# Schematic_v10.net
KiCad netlist of a schematic drawn in EAGLE
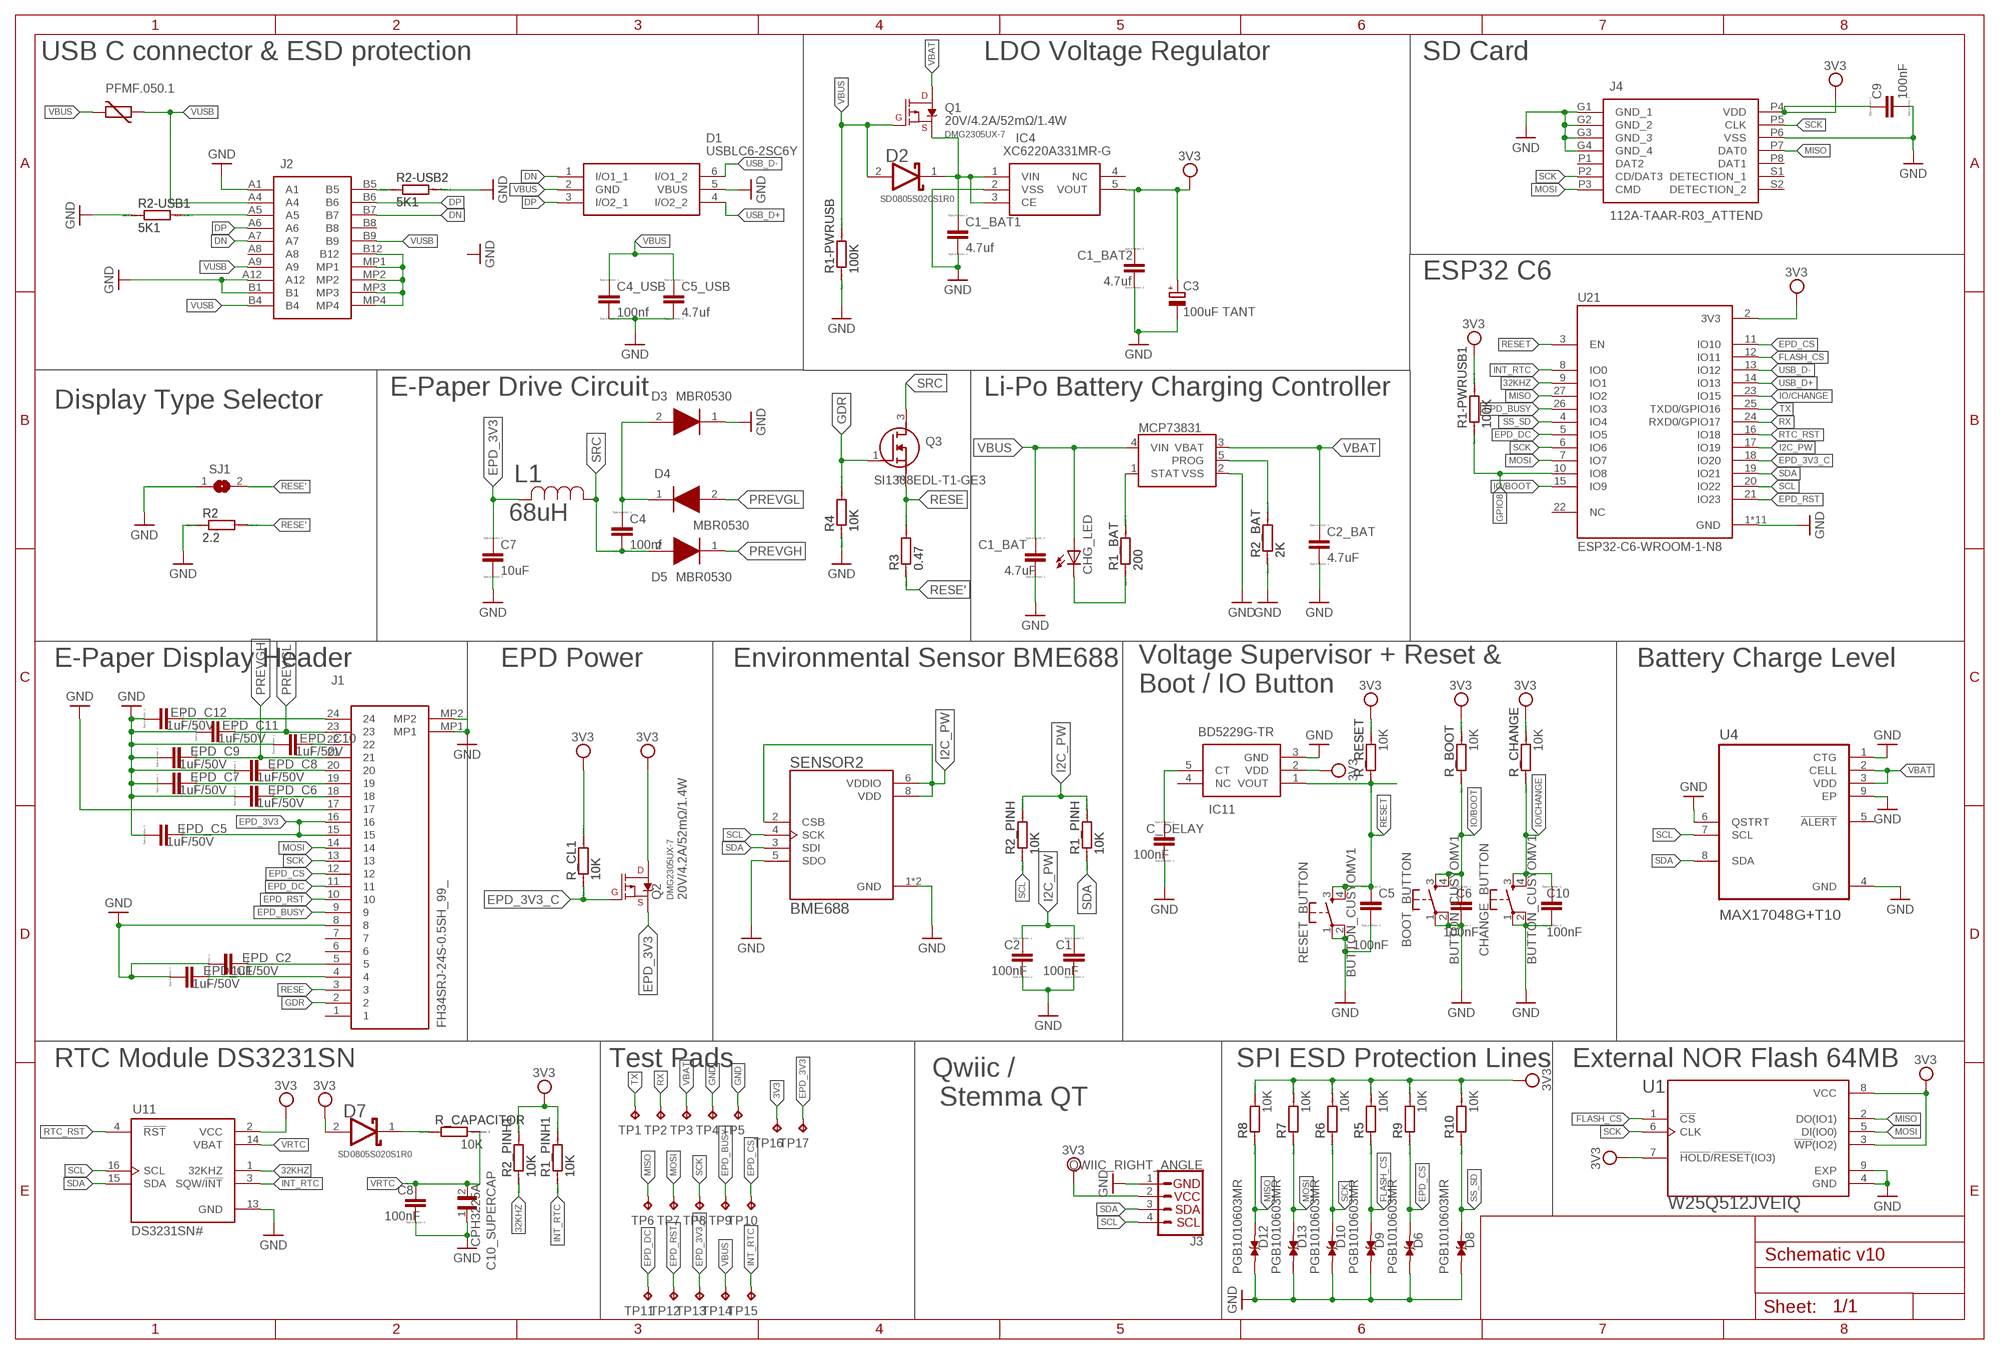
[diagram p0: schematic, sheet 1]

(export (version "E")
  (design (tool "Eeschema 10.0.6"))
  (components
    (comp (ref "BOOT_BUTTON")
      (value "BUTTON_CUSYOMV1")
      (footprint "eagle-import:MYBUTTON")
      (libsource (lib "eagle-import") (part "BUTTON_CUSYOMV1"))
    )
    (comp (ref "C1")
      (value "100nF")
      (footprint "eagle-import:EAGLE-LTSPICE_C0402")
      (libsource (lib "eagle-import") (part "EAGLE-LTSPICE_CC0402"))
    )
    (comp (ref "C1_BAT")
      (value "4.7uF")
      (footprint "eagle-import:EAGLE-LTSPICE_C0402")
      (libsource (lib "eagle-import") (part "EAGLE-LTSPICE_CC0402"))
    )
    (comp (ref "C1_BAT1")
      (value "4.7uf")
      (footprint "eagle-import:EAGLE-LTSPICE_C0402")
      (libsource (lib "eagle-import") (part "EAGLE-LTSPICE_CC0402"))
    )
    (comp (ref "C1_BAT2")
      (value "4.7uf")
      (footprint "eagle-import:EAGLE-LTSPICE_C0402")
      (libsource (lib "eagle-import") (part "EAGLE-LTSPICE_CC0402"))
    )
    (comp (ref "C2")
      (value "100nF")
      (footprint "eagle-import:EAGLE-LTSPICE_C0402")
      (libsource (lib "eagle-import") (part "EAGLE-LTSPICE_CC0402"))
    )
    (comp (ref "C2_BAT")
      (value "4.7uF")
      (footprint "eagle-import:EAGLE-LTSPICE_C0402")
      (libsource (lib "eagle-import") (part "EAGLE-LTSPICE_CC0402"))
    )
    (comp (ref "C3")
      (value "100uF TANT")
      (footprint "eagle-import:RCL_CT3528")
      (libsource (lib "eagle-import") (part "RCL_CPOL-EUCT3528"))
    )
    (comp (ref "C4")
      (value "100nf")
      (footprint "eagle-import:EAGLE-LTSPICE_C0402")
      (libsource (lib "eagle-import") (part "EAGLE-LTSPICE_CC0402"))
    )
    (comp (ref "C4_USB")
      (value "100nf")
      (footprint "eagle-import:EAGLE-LTSPICE_C0402")
      (libsource (lib "eagle-import") (part "EAGLE-LTSPICE_CC0402"))
    )
    (comp (ref "C5")
      (value "100nF")
      (footprint "eagle-import:EAGLE-LTSPICE_C0402")
      (libsource (lib "eagle-import") (part "EAGLE-LTSPICE_CC0402"))
    )
    (comp (ref "C5_USB")
      (value "4.7uf")
      (footprint "eagle-import:EAGLE-LTSPICE_C0402")
      (libsource (lib "eagle-import") (part "EAGLE-LTSPICE_CC0402"))
    )
    (comp (ref "C6")
      (value "100nF")
      (footprint "eagle-import:EAGLE-LTSPICE_C0402")
      (libsource (lib "eagle-import") (part "EAGLE-LTSPICE_CC0402"))
    )
    (comp (ref "C7")
      (value "10uF")
      (footprint "eagle-import:EAGLE-LTSPICE_C0402")
      (libsource (lib "eagle-import") (part "EAGLE-LTSPICE_CC0402"))
    )
    (comp (ref "C8")
      (value "100nF")
      (footprint "eagle-import:EAGLE-LTSPICE_C0402")
      (libsource (lib "eagle-import") (part "EAGLE-LTSPICE_CC0402"))
    )
    (comp (ref "C9")
      (value "100nF")
      (footprint "eagle-import:EAGLE-LTSPICE_C0402")
      (libsource (lib "eagle-import") (part "EAGLE-LTSPICE_CC0402"))
    )
    (comp (ref "C10")
      (value "100nF")
      (footprint "eagle-import:EAGLE-LTSPICE_C0402")
      (libsource (lib "eagle-import") (part "EAGLE-LTSPICE_CC0402"))
    )
    (comp (ref "C10_SUPERCAP")
      (value "CPH3225A")
      (footprint "eagle-import:CAPCP3225X100N")
      (fields (field (name "MF") "Seiko Instruments"))
      (libsource (lib "eagle-import") (part "CPH3225A"))
    )
    (comp (ref "CHANGE_BUTTON")
      (value "BUTTON_CUSYOMV1")
      (footprint "eagle-import:MYBUTTON")
      (libsource (lib "eagle-import") (part "BUTTON_CUSYOMV1"))
    )
    (comp (ref "CHG_LED")
      (value "ADAFRUIT_LEDCHIP-LED0603")
      (footprint "eagle-import:ADAFRUIT_CHIP-LED0603")
      (libsource (lib "eagle-import") (part "ADAFRUIT_LEDCHIP-LED0603"))
    )
    (comp (ref "C_DELAY")
      (value "100nF")
      (footprint "eagle-import:EAGLE-LTSPICE_C0402")
      (libsource (lib "eagle-import") (part "EAGLE-LTSPICE_CC0402"))
    )
    (comp (ref "D1")
      (value "USBLC6-2SC6Y")
      (footprint "eagle-import:SOT95P280X145-6N")
      (fields (field (name "MF") "STMicroelectronics"))
      (libsource (lib "eagle-import") (part "USBLC6-2SC6Y"))
    )
    (comp (ref "D2")
      (value "ESP32_WROVER_AVX---SD0805S020S1R0_AVX_SD0805S020S1R0_0_0AVX_SD0805S020S1R0_0_0")
      (footprint "SD0805S020S1R0")
      (fields
        (field (name "DIGIKEY_PART_NUMBER") "478-7800-1-ND")
        (field (name "MF") "AVX")
        (field (name "MOUSER_PART_NUMBER") "581-SD0805S020S1R0")
      )
      (libsource (lib "eagle-import") (part "ESP32_WROVER_AVX---SD0805S020S1R0_AVX_SD0805S020S1R0_0_0AVX_SD0805S020S1R0_0_0"))
    )
    (comp (ref "D3")
      (value "MBR0530")
      (footprint "eagle-import:SOD3716X135N")
      (fields (field (name "MF") "ON Semiconductor"))
      (libsource (lib "eagle-import") (part "MBR0530"))
    )
    (comp (ref "D4")
      (value "MBR0530")
      (footprint "eagle-import:SOD3716X135N")
      (fields (field (name "MF") "ON Semiconductor"))
      (libsource (lib "eagle-import") (part "MBR0530"))
    )
    (comp (ref "D5")
      (value "MBR0530")
      (footprint "eagle-import:SOD3716X135N")
      (fields (field (name "MF") "ON Semiconductor"))
      (libsource (lib "eagle-import") (part "MBR0530"))
    )
    (comp (ref "D6")
      (value "PGB1010603MR")
      (footprint "eagle-import:DIOC1608X36N")
      (fields (field (name "MF") "Littelfuse Inc."))
      (libsource (lib "eagle-import") (part "PGB1010603MR"))
    )
    (comp (ref "D7")
      (value "ESP32_WROVER_AVX---SD0805S020S1R0_AVX_SD0805S020S1R0_0_0AVX_SD0805S020S1R0_0_0")
      (footprint "SD0805S020S1R0")
      (fields
        (field (name "DIGIKEY_PART_NUMBER") "478-7800-1-ND")
        (field (name "MF") "AVX")
        (field (name "MOUSER_PART_NUMBER") "581-SD0805S020S1R0")
      )
      (libsource (lib "eagle-import") (part "ESP32_WROVER_AVX---SD0805S020S1R0_AVX_SD0805S020S1R0_0_0AVX_SD0805S020S1R0_0_0"))
    )
    (comp (ref "D8")
      (value "PGB1010603MR")
      (footprint "eagle-import:DIOC1608X36N")
      (fields (field (name "MF") "Littelfuse Inc."))
      (libsource (lib "eagle-import") (part "PGB1010603MR"))
    )
    (comp (ref "D9")
      (value "PGB1010603MR")
      (footprint "eagle-import:DIOC1608X36N")
      (fields (field (name "MF") "Littelfuse Inc."))
      (libsource (lib "eagle-import") (part "PGB1010603MR"))
    )
    (comp (ref "D10")
      (value "PGB1010603MR")
      (footprint "eagle-import:DIOC1608X36N")
      (fields (field (name "MF") "Littelfuse Inc."))
      (libsource (lib "eagle-import") (part "PGB1010603MR"))
    )
    (comp (ref "D12")
      (value "PGB1010603MR")
      (footprint "eagle-import:DIOC1608X36N")
      (fields (field (name "MF") "Littelfuse Inc."))
      (libsource (lib "eagle-import") (part "PGB1010603MR"))
    )
    (comp (ref "D13")
      (value "PGB1010603MR")
      (footprint "eagle-import:DIOC1608X36N")
      (fields (field (name "MF") "Littelfuse Inc."))
      (libsource (lib "eagle-import") (part "PGB1010603MR"))
    )
    (comp (ref "EPD_C1")
      (value "1uF/50V")
      (footprint "eagle-import:EAGLE-LTSPICE_C0402")
      (libsource (lib "eagle-import") (part "EAGLE-LTSPICE_CC0402"))
    )
    (comp (ref "EPD_C2")
      (value "1uF/50V")
      (footprint "eagle-import:EAGLE-LTSPICE_C0402")
      (libsource (lib "eagle-import") (part "EAGLE-LTSPICE_CC0402"))
    )
    (comp (ref "EPD_C5")
      (value "1uF/50V")
      (footprint "eagle-import:EAGLE-LTSPICE_C0402")
      (libsource (lib "eagle-import") (part "EAGLE-LTSPICE_CC0402"))
    )
    (comp (ref "EPD_C6")
      (value "1uF/50V")
      (footprint "eagle-import:EAGLE-LTSPICE_C0402")
      (libsource (lib "eagle-import") (part "EAGLE-LTSPICE_CC0402"))
    )
    (comp (ref "EPD_C7")
      (value "1uF/50V")
      (footprint "eagle-import:EAGLE-LTSPICE_C0402")
      (libsource (lib "eagle-import") (part "EAGLE-LTSPICE_CC0402"))
    )
    (comp (ref "EPD_C8")
      (value "1uF/50V")
      (footprint "eagle-import:EAGLE-LTSPICE_C0402")
      (libsource (lib "eagle-import") (part "EAGLE-LTSPICE_CC0402"))
    )
    (comp (ref "EPD_C9")
      (value "1uF/50V")
      (footprint "eagle-import:EAGLE-LTSPICE_C0402")
      (libsource (lib "eagle-import") (part "EAGLE-LTSPICE_CC0402"))
    )
    (comp (ref "EPD_C10")
      (value "1uF/50V")
      (footprint "eagle-import:EAGLE-LTSPICE_C0402")
      (libsource (lib "eagle-import") (part "EAGLE-LTSPICE_CC0402"))
    )
    (comp (ref "EPD_C11")
      (value "1uF/50V")
      (footprint "eagle-import:EAGLE-LTSPICE_C0402")
      (libsource (lib "eagle-import") (part "EAGLE-LTSPICE_CC0402"))
    )
    (comp (ref "EPD_C12")
      (value "1uF/50V")
      (footprint "eagle-import:EAGLE-LTSPICE_C0402")
      (libsource (lib "eagle-import") (part "EAGLE-LTSPICE_CC0402"))
    )
    (comp (ref "IC4")
      (value "XC6220A331MR-G")
      (footprint "eagle-import:SOT95P280X120-5N")
      (fields (field (name "MOUSER_PART_NUMBER") "865-XC6220A331MR-G"))
      (libsource (lib "eagle-import") (part "XC6220A331MR-G"))
    )
    (comp (ref "IC11")
      (value "BD5229G-TR")
      (footprint "eagle-import:SOT95P280X125-5N")
      (fields (field (name "MOUSER_PART_NUMBER") "755-BD5229G-TR"))
      (libsource (lib "eagle-import") (part "BD5229G-TR"))
    )
    (comp (ref "J1")
      (value "FH34SRJ-24S-0.5SH_99_")
      (footprint "eagle-import:FH34SRJ24S05SH99")
      (fields
        (field (name "MANUFACTURER_PART_NUMBER") "FH34SRJ-24S-0.5SH(99)")
        (field (name "MOUSER_PART_NUMBER") "798-FH34SRJ24S05SH99")
      )
      (libsource (lib "eagle-import") (part "FH34SRJ-24S-0.5SH_99_"))
    )
    (comp (ref "J2")
      (value "SAMACSYS_PARTS_USB4110-GF-A")
      (footprint "eagle-import:SAMACSYS_PARTS_USB4110GFA")
      (fields
        (field (name "MANUFACTURER_PART_NUMBER") "USB4110-GF-A")
        (field (name "MOUSER_PART_NUMBER") "640-USB4110-GF-A")
      )
      (libsource (lib "eagle-import") (part "SAMACSYS_PARTS_USB4110-GF-A"))
    )
    (comp (ref "J3")
      (value "QWIIC_RIGHT_ANGLE")
      (footprint "eagle-import:JST04_1MM_RA")
      (libsource (lib "eagle-import") (part "QWIIC_CONNECTORJS-1MM"))
    )
    (comp (ref "J4")
      (value "112A-TAAR-R03_ATTEND")
      (footprint "eagle-import:112ATAARR03ATTEND")
      (fields (field (name "MANUFACTURER_PART_NUMBER") "112A-TAAR-R03 ATTEND"))
      (libsource (lib "eagle-import") (part "112A-TAAR-R03_ATTEND"))
    )
    (comp (ref "L1")
      (value "68uH")
      (footprint "eagle-import:IND_4828-WE-TPC_WRE")
      (fields
        (field (name "MANUFACTURER_PART_NUMBER") "744043680")
        (field (name "COPYRIGHT") "Copyright (C) 2024 Ultra Librarian. All rights reserved.")
      )
      (libsource (lib "eagle-import") (part "744043680IND_4828-WE-TPC_WRE"))
    )
    (comp (ref "MCP73831")
      (value "ESP32_WROVER_SPARKFUN-IC-POWER_MCP73831")
      (footprint "eagle-import:ESP32_WROVER_SPARKFUN-IC-POWER_SOT23-5")
      (libsource (lib "eagle-import") (part "ESP32_WROVER_SPARKFUN-IC-POWER_MCP73831"))
    )
    (comp (ref "PFMF.050.1")
      (value "ESP32C6_VARISTORCN1812")
      (footprint "eagle-import:ESP32C6_VARISTOR_CT_CN1812")
      (libsource (lib "eagle-import") (part "ESP32C6_VARISTORCN1812"))
    )
    (comp (ref "Q1")
      (value "20V/4.2A/52mΩ/1.4W")
      (footprint "DMG2305UX-7")
      (libsource (lib "eagle-import") (part "ESP32_WROVER_SPARKFUN-DISCRETESEMI_MOSFET_PCH-DMG2305UX-7"))
    )
    (comp (ref "Q2")
      (value "20V/4.2A/52mΩ/1.4W")
      (footprint "DMG2305UX-7")
      (libsource (lib "eagle-import") (part "ESP32_WROVER_SPARKFUN-DISCRETESEMI_MOSFET_PCH-DMG2305UX-7"))
    )
    (comp (ref "Q3")
      (value "SI1308EDL-T1-GE3")
      (footprint "eagle-import:SOT65P210X110-3N")
      (fields (field (name "MF") "Vishay Siliconix"))
      (libsource (lib "eagle-import") (part "SI1308EDL-T1-GE3"))
    )
    (comp (ref "R1-PWRUSB")
      (value "100K")
      (footprint "eagle-import:ESP32_WROVER_EAGLE-LTSPICE_R0402")
      (libsource (lib "eagle-import") (part "ESP32_WROVER_EAGLE-LTSPICE_RR0402"))
    )
    (comp (ref "R1-PWRUSB1")
      (value "100K")
      (footprint "eagle-import:ESP32_WROVER_EAGLE-LTSPICE_R0402")
      (libsource (lib "eagle-import") (part "ESP32_WROVER_EAGLE-LTSPICE_RR0402"))
    )
    (comp (ref "R1_BAT")
      (value "200")
      (footprint "eagle-import:ESP32_WROVER_EAGLE-LTSPICE_R0402")
      (libsource (lib "eagle-import") (part "ESP32_WROVER_EAGLE-LTSPICE_RR0402"))
    )
    (comp (ref "R1_PINH")
      (value "10K")
      (footprint "eagle-import:ESP32_WROVER_EAGLE-LTSPICE_R0402")
      (libsource (lib "eagle-import") (part "ESP32_WROVER_EAGLE-LTSPICE_RR0402"))
    )
    (comp (ref "R1_PINH1")
      (value "10K")
      (footprint "eagle-import:ESP32_WROVER_EAGLE-LTSPICE_R0402")
      (libsource (lib "eagle-import") (part "ESP32_WROVER_EAGLE-LTSPICE_RR0402"))
    )
    (comp (ref "R2")
      (value "2.2")
      (footprint "eagle-import:ESP32_WROVER_EAGLE-LTSPICE_R0402")
      (libsource (lib "eagle-import") (part "ESP32_WROVER_EAGLE-LTSPICE_RR0402"))
    )
    (comp (ref "R2-USB1")
      (value "5K1")
      (footprint "eagle-import:ESP32_WROVER_EAGLE-LTSPICE_R0402")
      (libsource (lib "eagle-import") (part "ESP32_WROVER_EAGLE-LTSPICE_RR0402"))
    )
    (comp (ref "R2-USB2")
      (value "5K1")
      (footprint "eagle-import:ESP32_WROVER_EAGLE-LTSPICE_R0402")
      (libsource (lib "eagle-import") (part "ESP32_WROVER_EAGLE-LTSPICE_RR0402"))
    )
    (comp (ref "R2_BAT")
      (value "2K")
      (footprint "eagle-import:ESP32_WROVER_EAGLE-LTSPICE_R0402")
      (libsource (lib "eagle-import") (part "ESP32_WROVER_EAGLE-LTSPICE_RR0402"))
    )
    (comp (ref "R2_PINH")
      (value "10K")
      (footprint "eagle-import:ESP32_WROVER_EAGLE-LTSPICE_R0402")
      (libsource (lib "eagle-import") (part "ESP32_WROVER_EAGLE-LTSPICE_RR0402"))
    )
    (comp (ref "R2_PINH1")
      (value "10K")
      (footprint "eagle-import:ESP32_WROVER_EAGLE-LTSPICE_R0402")
      (libsource (lib "eagle-import") (part "ESP32_WROVER_EAGLE-LTSPICE_RR0402"))
    )
    (comp (ref "R3")
      (value "0.47")
      (footprint "eagle-import:ESP32_WROVER_EAGLE-LTSPICE_R0402")
      (libsource (lib "eagle-import") (part "ESP32_WROVER_EAGLE-LTSPICE_RR0402"))
    )
    (comp (ref "R4")
      (value "10K")
      (footprint "eagle-import:ESP32_WROVER_EAGLE-LTSPICE_R0402")
      (libsource (lib "eagle-import") (part "ESP32_WROVER_EAGLE-LTSPICE_RR0402"))
    )
    (comp (ref "R5")
      (value "10K")
      (footprint "eagle-import:ESP32_WROVER_EAGLE-LTSPICE_R0402")
      (libsource (lib "eagle-import") (part "ESP32_WROVER_EAGLE-LTSPICE_RR0402"))
    )
    (comp (ref "R6")
      (value "10K")
      (footprint "eagle-import:ESP32_WROVER_EAGLE-LTSPICE_R0402")
      (libsource (lib "eagle-import") (part "ESP32_WROVER_EAGLE-LTSPICE_RR0402"))
    )
    (comp (ref "R7")
      (value "10K")
      (footprint "eagle-import:ESP32_WROVER_EAGLE-LTSPICE_R0402")
      (libsource (lib "eagle-import") (part "ESP32_WROVER_EAGLE-LTSPICE_RR0402"))
    )
    (comp (ref "R8")
      (value "10K")
      (footprint "eagle-import:ESP32_WROVER_EAGLE-LTSPICE_R0402")
      (libsource (lib "eagle-import") (part "ESP32_WROVER_EAGLE-LTSPICE_RR0402"))
    )
    (comp (ref "R9")
      (value "10K")
      (footprint "eagle-import:ESP32_WROVER_EAGLE-LTSPICE_R0402")
      (libsource (lib "eagle-import") (part "ESP32_WROVER_EAGLE-LTSPICE_RR0402"))
    )
    (comp (ref "R10")
      (value "10K")
      (footprint "eagle-import:ESP32_WROVER_EAGLE-LTSPICE_R0402")
      (libsource (lib "eagle-import") (part "ESP32_WROVER_EAGLE-LTSPICE_RR0402"))
    )
    (comp (ref "RESET_BUTTON")
      (value "BUTTON_CUSYOMV1")
      (footprint "eagle-import:MYBUTTON")
      (libsource (lib "eagle-import") (part "BUTTON_CUSYOMV1"))
    )
    (comp (ref "R_BOOT")
      (value "10K")
      (footprint "eagle-import:ESP32_WROVER_EAGLE-LTSPICE_R0402")
      (libsource (lib "eagle-import") (part "ESP32_WROVER_EAGLE-LTSPICE_RR0402"))
    )
    (comp (ref "R_CAPACITOR")
      (value "10K")
      (footprint "eagle-import:ESP32_WROVER_EAGLE-LTSPICE_R0402")
      (libsource (lib "eagle-import") (part "ESP32_WROVER_EAGLE-LTSPICE_RR0402"))
    )
    (comp (ref "R_CHANGE")
      (value "10K")
      (footprint "eagle-import:ESP32_WROVER_EAGLE-LTSPICE_R0402")
      (libsource (lib "eagle-import") (part "ESP32_WROVER_EAGLE-LTSPICE_RR0402"))
    )
    (comp (ref "R_CL1")
      (value "10K")
      (footprint "eagle-import:ESP32_WROVER_EAGLE-LTSPICE_R0402")
      (libsource (lib "eagle-import") (part "ESP32_WROVER_EAGLE-LTSPICE_RR0402"))
    )
    (comp (ref "R_RESET")
      (value "10K")
      (footprint "eagle-import:ESP32_WROVER_EAGLE-LTSPICE_R0402")
      (libsource (lib "eagle-import") (part "ESP32_WROVER_EAGLE-LTSPICE_RR0402"))
    )
    (comp (ref "SENSOR2")
      (value "BME688")
      (footprint "eagle-import:ESP32_WROVER_BME680_PSON80P300X300X100-8N")
      (fields (field (name "MF") "Bosch Sensortec") (field (name "MP") "BME680"))
      (libsource (lib "eagle-import") (part "ESP32_WROVER_BME680_BME680"))
    )
    (comp (ref "SJ1") (value "SJ") (footprint "eagle-import:SJ") (libsource (lib "eagle-import") (part "SJ")))
    (comp (ref "TP1")
      (value "TPTP20R")
      (footprint "eagle-import:TP20R")
      (libsource (lib "eagle-import") (part "TPTP20R"))
    )
    (comp (ref "TP2")
      (value "TPTP20R")
      (footprint "eagle-import:TP20R")
      (libsource (lib "eagle-import") (part "TPTP20R"))
    )
    (comp (ref "TP3")
      (value "TPTP20R")
      (footprint "eagle-import:TP20R")
      (libsource (lib "eagle-import") (part "TPTP20R"))
    )
    (comp (ref "TP4")
      (value "TPTP20R")
      (footprint "eagle-import:TP20R")
      (libsource (lib "eagle-import") (part "TPTP20R"))
    )
    (comp (ref "TP5")
      (value "TPTP20R")
      (footprint "eagle-import:TP20R")
      (libsource (lib "eagle-import") (part "TPTP20R"))
    )
    (comp (ref "TP6")
      (value "TPTP20R")
      (footprint "eagle-import:TP20R")
      (libsource (lib "eagle-import") (part "TPTP20R"))
    )
    (comp (ref "TP7")
      (value "TPTP20R")
      (footprint "eagle-import:TP20R")
      (libsource (lib "eagle-import") (part "TPTP20R"))
    )
    (comp (ref "TP8")
      (value "TPTP20R")
      (footprint "eagle-import:TP20R")
      (libsource (lib "eagle-import") (part "TPTP20R"))
    )
    (comp (ref "TP9")
      (value "TPTP20R")
      (footprint "eagle-import:TP20R")
      (libsource (lib "eagle-import") (part "TPTP20R"))
    )
    (comp (ref "TP10")
      (value "TPTP20R")
      (footprint "eagle-import:TP20R")
      (libsource (lib "eagle-import") (part "TPTP20R"))
    )
    (comp (ref "TP11")
      (value "TPTP20R")
      (footprint "eagle-import:TP20R")
      (libsource (lib "eagle-import") (part "TPTP20R"))
    )
    (comp (ref "TP12")
      (value "TPTP20R")
      (footprint "eagle-import:TP20R")
      (libsource (lib "eagle-import") (part "TPTP20R"))
    )
    (comp (ref "TP13")
      (value "TPTP20R")
      (footprint "eagle-import:TP20R")
      (libsource (lib "eagle-import") (part "TPTP20R"))
    )
    (comp (ref "TP14")
      (value "TPTP20R")
      (footprint "eagle-import:TP20R")
      (libsource (lib "eagle-import") (part "TPTP20R"))
    )
    (comp (ref "TP15")
      (value "TPTP20R")
      (footprint "eagle-import:TP20R")
      (libsource (lib "eagle-import") (part "TPTP20R"))
    )
    (comp (ref "TP16")
      (value "TPTP20R")
      (footprint "eagle-import:TP20R")
      (libsource (lib "eagle-import") (part "TPTP20R"))
    )
    (comp (ref "TP17")
      (value "TPTP20R")
      (footprint "eagle-import:TP20R")
      (libsource (lib "eagle-import") (part "TPTP20R"))
    )
    (comp (ref "U1")
      (value "W25Q512JVEIQ")
      (footprint "eagle-import:SON127P600X800X80-9N")
      (fields (field (name "MF") "Winbond Electronics"))
      (libsource (lib "eagle-import") (part "W25Q512JVEIQ"))
    )
    (comp (ref "U4")
      (value "MAX17048G+T10")
      (footprint "eagle-import:SON50P200X200X80-9N")
      (fields (field (name "MF") "Analog Devices"))
      (libsource (lib "eagle-import") (part "MAX17048G+T10"))
    )
    (comp (ref "U11")
      (value "DS3231SN#")
      (footprint "eagle-import:SOIC127P1032X265-16N")
      (fields (field (name "MF") "Analog Devices"))
      (libsource (lib "eagle-import") (part "DS3231SN#"))
    )
    (comp (ref "U21")
      (value "ESP32-C6-WROOM-1-N8")
      (footprint "eagle-import:XCVR_ESP32-C6-WROOM-1-N8")
      (fields (field (name "MF") "Espressif Systems"))
      (libsource (lib "eagle-import") (part "ESP32-C6-WROOM-1-N8"))
    )
  )
  (nets
    (net (code "1") (name "3V3") (class "Default")
      (node (ref "C1_BAT2") (pin "1") (pinfunction "1_1") (pintype "passive"))
      (node (ref "C3") (pin "+") (pinfunction "+_+") (pintype "passive"))
      (node (ref "C9") (pin "1") (pinfunction "1_1") (pintype "passive"))
      (node (ref "D7") (pin "2") (pinfunction "ANODE_2") (pintype "bidirectional"))
      (node (ref "IC11") (pin "2") (pinfunction "VDD_2") (pintype "bidirectional"))
      (node (ref "IC4") (pin "5") (pinfunction "VOUT_5") (pintype "bidirectional"))
      (node (ref "J3") (pin "2") (pinfunction "2_2") (pintype "power_in"))
      (node (ref "J4") (pin "P4") (pinfunction "VDD_P4") (pintype "bidirectional"))
      (node (ref "Q2") (pin "3") (pinfunction "D_3") (pintype "bidirectional"))
      (node (ref "R1-PWRUSB1") (pin "2") (pinfunction "2_2") (pintype "passive"))
      (node (ref "R10") (pin "2") (pinfunction "2_2") (pintype "passive"))
      (node (ref "R1_PINH1") (pin "2") (pinfunction "2_2") (pintype "passive"))
      (node (ref "R2_PINH1") (pin "2") (pinfunction "2_2") (pintype "passive"))
      (node (ref "R5") (pin "2") (pinfunction "2_2") (pintype "passive"))
      (node (ref "R6") (pin "2") (pinfunction "2_2") (pintype "passive"))
      (node (ref "R7") (pin "2") (pinfunction "2_2") (pintype "passive"))
      (node (ref "R8") (pin "2") (pinfunction "2_2") (pintype "passive"))
      (node (ref "R9") (pin "2") (pinfunction "2_2") (pintype "passive"))
      (node (ref "R_BOOT") (pin "2") (pinfunction "2_2") (pintype "passive"))
      (node (ref "R_CHANGE") (pin "2") (pinfunction "2_2") (pintype "passive"))
      (node (ref "R_CL1") (pin "2") (pinfunction "2_2") (pintype "passive"))
      (node (ref "R_RESET") (pin "2") (pinfunction "2_2") (pintype "passive"))
      (node (ref "TP16") (pin "TP") (pinfunction "TP_TP") (pintype "input"))
      (node (ref "U1") (pin "3") (pinfunction "~{WP}(IO2)_3") (pintype "bidirectional"))
      (node (ref "U1") (pin "7") (pinfunction "~{HOLD}/~{RESET}(IO3)_7") (pintype "bidirectional"))
      (node (ref "U1") (pin "8") (pinfunction "VCC_8") (pintype "power_in"))
      (node (ref "U11") (pin "2") (pinfunction "VCC_2") (pintype "power_in"))
      (node (ref "U21") (pin "2") (pinfunction "3V3_2") (pintype "power_in"))
    )
    (net (code "2") (name "32KHZ") (class "Default")
      (node (ref "R2_PINH1") (pin "1") (pinfunction "1_1") (pintype "passive"))
      (node (ref "U11") (pin "1") (pinfunction "32KHZ_1") (pintype "output"))
      (node (ref "U21") (pin "9") (pinfunction "IO1_9") (pintype "bidirectional"))
    )
    (net (code "3") (name "DN") (class "Default")
      (node (ref "D1") (pin "1") (pinfunction "I/O1_1_1") (pintype "bidirectional"))
      (node (ref "J2") (pin "A7") (pinfunction "A7_A7") (pintype "bidirectional"))
      (node (ref "J2") (pin "B7") (pinfunction "B7_B7") (pintype "bidirectional"))
    )
    (net (code "4") (name "DP") (class "Default")
      (node (ref "D1") (pin "3") (pinfunction "I/O2_1_3") (pintype "bidirectional"))
      (node (ref "J2") (pin "A6") (pinfunction "A6_A6") (pintype "bidirectional"))
      (node (ref "J2") (pin "B6") (pinfunction "B6_B6") (pintype "bidirectional"))
    )
    (net (code "5") (name "EPD_3V3") (class "Default")
      (node (ref "C7") (pin "1") (pinfunction "1_1") (pintype "passive"))
      (node (ref "EPD_C5") (pin "2") (pinfunction "2_2") (pintype "passive"))
      (node (ref "J1") (pin "15") (pinfunction "15_15") (pintype "bidirectional"))
      (node (ref "J1") (pin "16") (pinfunction "16_16") (pintype "bidirectional"))
      (node (ref "L1") (pin "2") (pinfunction "2_2") (pintype "passive"))
      (node (ref "Q2") (pin "2") (pinfunction "S_2") (pintype "bidirectional"))
      (node (ref "TP17") (pin "TP") (pinfunction "TP_TP") (pintype "input"))
    )
    (net (code "6") (name "EPD_3V3_C") (class "Default")
      (node (ref "Q2") (pin "1") (pinfunction "G_1") (pintype "bidirectional"))
      (node (ref "R_CL1") (pin "1") (pinfunction "1_1") (pintype "passive"))
      (node (ref "TP13") (pin "TP") (pinfunction "TP_TP") (pintype "input"))
      (node (ref "U21") (pin "18") (pinfunction "IO20_18") (pintype "bidirectional"))
    )
    (net (code "7") (name "EPD_BUSY") (class "Default")
      (node (ref "J1") (pin "9") (pinfunction "9_9") (pintype "bidirectional"))
      (node (ref "TP9") (pin "TP") (pinfunction "TP_TP") (pintype "input"))
      (node (ref "U21") (pin "26") (pinfunction "IO3_26") (pintype "bidirectional"))
    )
    (net (code "8") (name "EPD_CS") (class "Default")
      (node (ref "D6") (pin "2") (pinfunction "2_2") (pintype "passive"))
      (node (ref "J1") (pin "12") (pinfunction "12_12") (pintype "bidirectional"))
      (node (ref "R9") (pin "1") (pinfunction "1_1") (pintype "passive"))
      (node (ref "TP10") (pin "TP") (pinfunction "TP_TP") (pintype "input"))
      (node (ref "U21") (pin "11") (pinfunction "IO10_11") (pintype "bidirectional"))
    )
    (net (code "9") (name "EPD_DC") (class "Default")
      (node (ref "J1") (pin "11") (pinfunction "11_11") (pintype "bidirectional"))
      (node (ref "TP11") (pin "TP") (pinfunction "TP_TP") (pintype "input"))
      (node (ref "U21") (pin "5") (pinfunction "IO5_5") (pintype "bidirectional"))
    )
    (net (code "10") (name "EPD_RST") (class "Default")
      (node (ref "J1") (pin "10") (pinfunction "10_10") (pintype "bidirectional"))
      (node (ref "TP12") (pin "TP") (pinfunction "TP_TP") (pintype "input"))
      (node (ref "U21") (pin "21") (pinfunction "IO23_21") (pintype "bidirectional"))
    )
    (net (code "11") (name "FLASH_CS") (class "Default")
      (node (ref "D9") (pin "2") (pinfunction "2_2") (pintype "passive"))
      (node (ref "R5") (pin "1") (pinfunction "1_1") (pintype "passive"))
      (node (ref "U1") (pin "1") (pinfunction "~{CS}_1") (pintype "input"))
      (node (ref "U21") (pin "12") (pinfunction "IO11_12") (pintype "bidirectional"))
    )
    (net (code "12") (name "GDR") (class "Default")
      (node (ref "J1") (pin "2") (pinfunction "2_2") (pintype "bidirectional"))
      (node (ref "Q3") (pin "1") (pinfunction "G_1") (pintype "bidirectional"))
      (node (ref "R4") (pin "2") (pinfunction "2_2") (pintype "passive"))
    )
    (net (code "13") (name "GND") (class "Default")
      (node (ref "BOOT_BUTTON") (pin "1") (pinfunction "1_1") (pintype "passive"))
      (node (ref "BOOT_BUTTON") (pin "2") (pinfunction "2_2") (pintype "passive"))
      (node (ref "C1") (pin "2") (pinfunction "2_2") (pintype "passive"))
      (node (ref "C10") (pin "2") (pinfunction "2_2") (pintype "passive"))
      (node (ref "C10_SUPERCAP") (pin "1") (pinfunction "1_1") (pintype "passive"))
      (node (ref "C1_BAT") (pin "2") (pinfunction "2_2") (pintype "passive"))
      (node (ref "C1_BAT1") (pin "2") (pinfunction "2_2") (pintype "passive"))
      (node (ref "C1_BAT2") (pin "2") (pinfunction "2_2") (pintype "passive"))
      (node (ref "C2") (pin "2") (pinfunction "2_2") (pintype "passive"))
      (node (ref "C2_BAT") (pin "2") (pinfunction "2_2") (pintype "passive"))
      (node (ref "C3") (pin "-") (pinfunction "-_-") (pintype "passive"))
      (node (ref "C4_USB") (pin "2") (pinfunction "2_2") (pintype "passive"))
      (node (ref "C5") (pin "2") (pinfunction "2_2") (pintype "passive"))
      (node (ref "C5_USB") (pin "2") (pinfunction "2_2") (pintype "passive"))
      (node (ref "C6") (pin "2") (pinfunction "2_2") (pintype "passive"))
      (node (ref "C7") (pin "2") (pinfunction "2_2") (pintype "passive"))
      (node (ref "C8") (pin "2") (pinfunction "2_2") (pintype "passive"))
      (node (ref "C9") (pin "2") (pinfunction "2_2") (pintype "passive"))
      (node (ref "CHANGE_BUTTON") (pin "1") (pinfunction "1_1") (pintype "passive"))
      (node (ref "CHANGE_BUTTON") (pin "2") (pinfunction "2_2") (pintype "passive"))
      (node (ref "C_DELAY") (pin "2") (pinfunction "2_2") (pintype "passive"))
      (node (ref "D1") (pin "5") (pinfunction "VBUS_5") (pintype "bidirectional"))
      (node (ref "D10") (pin "1") (pinfunction "1_1") (pintype "passive"))
      (node (ref "D12") (pin "1") (pinfunction "1_1") (pintype "passive"))
      (node (ref "D13") (pin "1") (pinfunction "1_1") (pintype "passive"))
      (node (ref "D3") (pin "1") (pinfunction "K_1") (pintype "bidirectional"))
      (node (ref "D6") (pin "1") (pinfunction "1_1") (pintype "passive"))
      (node (ref "D8") (pin "1") (pinfunction "1_1") (pintype "passive"))
      (node (ref "D9") (pin "1") (pinfunction "1_1") (pintype "passive"))
      (node (ref "EPD_C1") (pin "1") (pinfunction "1_1") (pintype "passive"))
      (node (ref "EPD_C10") (pin "1") (pinfunction "1_1") (pintype "passive"))
      (node (ref "EPD_C11") (pin "1") (pinfunction "1_1") (pintype "passive"))
      (node (ref "EPD_C12") (pin "1") (pinfunction "1_1") (pintype "passive"))
      (node (ref "EPD_C2") (pin "1") (pinfunction "1_1") (pintype "passive"))
      (node (ref "EPD_C5") (pin "1") (pinfunction "1_1") (pintype "passive"))
      (node (ref "EPD_C6") (pin "1") (pinfunction "1_1") (pintype "passive"))
      (node (ref "EPD_C7") (pin "1") (pinfunction "1_1") (pintype "passive"))
      (node (ref "EPD_C8") (pin "1") (pinfunction "1_1") (pintype "passive"))
      (node (ref "EPD_C9") (pin "1") (pinfunction "1_1") (pintype "passive"))
      (node (ref "IC11") (pin "3") (pinfunction "GND_3") (pintype "bidirectional"))
      (node (ref "IC4") (pin "2") (pinfunction "VSS_2") (pintype "bidirectional"))
      (node (ref "J1") (pin "17") (pinfunction "17_17") (pintype "bidirectional"))
      (node (ref "J1") (pin "8") (pinfunction "8_8") (pintype "bidirectional"))
      (node (ref "J1") (pin "MP1") (pinfunction "MP1_MP1") (pintype "bidirectional"))
      (node (ref "J1") (pin "MP2") (pinfunction "MP2_MP2") (pintype "bidirectional"))
      (node (ref "J2") (pin "A1") (pinfunction "A1_A1") (pintype "bidirectional"))
      (node (ref "J2") (pin "A12") (pinfunction "A12_A12") (pintype "bidirectional"))
      (node (ref "J2") (pin "B1") (pinfunction "B1_B1") (pintype "bidirectional"))
      (node (ref "J3") (pin "1") (pinfunction "1_1") (pintype "power_in"))
      (node (ref "J4") (pin "G1") (pinfunction "GND_1_G1") (pintype "bidirectional"))
      (node (ref "J4") (pin "G2") (pinfunction "GND_2_G2") (pintype "bidirectional"))
      (node (ref "J4") (pin "G3") (pinfunction "GND_3_G3") (pintype "bidirectional"))
      (node (ref "J4") (pin "G4") (pinfunction "GND_4_G4") (pintype "bidirectional"))
      (node (ref "J4") (pin "P6") (pinfunction "VSS_P6") (pintype "bidirectional"))
      (node (ref "MCP73831") (pin "2") (pinfunction "VSS_2") (pintype "power_in"))
      (node (ref "R1-PWRUSB") (pin "1") (pinfunction "1_1") (pintype "passive"))
      (node (ref "R2") (pin "1") (pinfunction "1_1") (pintype "passive"))
      (node (ref "R2-USB1") (pin "1") (pinfunction "1_1") (pintype "passive"))
      (node (ref "R2-USB2") (pin "2") (pinfunction "2_2") (pintype "passive"))
      (node (ref "R2_BAT") (pin "1") (pinfunction "1_1") (pintype "passive"))
      (node (ref "R4") (pin "1") (pinfunction "1_1") (pintype "passive"))
      (node (ref "RESET_BUTTON") (pin "1") (pinfunction "1_1") (pintype "passive"))
      (node (ref "RESET_BUTTON") (pin "2") (pinfunction "2_2") (pintype "passive"))
      (node (ref "SENSOR2") (pin "1") (pinfunction "GND_1") (pintype "power_in"))
      (node (ref "SENSOR2") (pin "5") (pinfunction "SDO_5") (pintype "bidirectional"))
      (node (ref "SENSOR2") (pin "7") (pinfunction "GND_7") (pintype "power_in"))
      (node (ref "SJ1") (pin "1") (pinfunction "1_1") (pintype "passive"))
      (node (ref "TP4") (pin "TP") (pinfunction "TP_TP") (pintype "input"))
      (node (ref "TP5") (pin "TP") (pinfunction "TP_TP") (pintype "input"))
      (node (ref "U1") (pin "4") (pinfunction "GND_4") (pintype "power_in"))
      (node (ref "U1") (pin "9") (pinfunction "EXP_9") (pintype "passive"))
      (node (ref "U11") (pin "13") (pinfunction "GND_13") (pintype "power_in"))
      (node (ref "U21") (pin "1") (pinfunction "GND_1") (pintype "power_in"))
      (node (ref "U21") (pin "28") (pinfunction "GND_28") (pintype "power_in"))
      (node (ref "U21") (pin "29_1") (pinfunction "GND_29_1") (pintype "power_in"))
      (node (ref "U21") (pin "29_2") (pinfunction "GND_29_2") (pintype "power_in"))
      (node (ref "U21") (pin "29_3") (pinfunction "GND_29_3") (pintype "power_in"))
      (node (ref "U21") (pin "29_4") (pinfunction "GND_29_4") (pintype "power_in"))
      (node (ref "U21") (pin "29_5") (pinfunction "GND_29_5") (pintype "power_in"))
      (node (ref "U21") (pin "29_6") (pinfunction "GND_29_6") (pintype "power_in"))
      (node (ref "U21") (pin "29_7") (pinfunction "GND_29_7") (pintype "power_in"))
      (node (ref "U21") (pin "29_8") (pinfunction "GND_29_8") (pintype "power_in"))
      (node (ref "U21") (pin "29_9") (pinfunction "GND_29_9") (pintype "power_in"))
      (node (ref "U4") (pin "1") (pinfunction "CTG_1") (pintype "power_in"))
      (node (ref "U4") (pin "4") (pinfunction "GND_4") (pintype "power_in"))
      (node (ref "U4") (pin "6") (pinfunction "QSTRT_6") (pintype "input"))
      (node (ref "U4") (pin "9") (pinfunction "EP_9") (pintype "power_in"))
    )
    (net (code "14") (name "GPIO8") (class "Default")
      (node (ref "R1-PWRUSB1") (pin "1") (pinfunction "1_1") (pintype "passive"))
      (node (ref "U21") (pin "10") (pinfunction "IO8_10") (pintype "bidirectional"))
    )
    (net (code "15") (name "I2C_PW") (class "Default")
      (node (ref "C1") (pin "1") (pinfunction "1_1") (pintype "passive"))
      (node (ref "C2") (pin "1") (pinfunction "1_1") (pintype "passive"))
      (node (ref "R1_PINH") (pin "2") (pinfunction "2_2") (pintype "passive"))
      (node (ref "R2_PINH") (pin "2") (pinfunction "2_2") (pintype "passive"))
      (node (ref "SENSOR2") (pin "2") (pinfunction "CSB_2") (pintype "input"))
      (node (ref "SENSOR2") (pin "6") (pinfunction "VDDIO_6") (pintype "power_in"))
      (node (ref "SENSOR2") (pin "8") (pinfunction "VDD_8") (pintype "power_in"))
      (node (ref "U21") (pin "17") (pinfunction "IO19_17") (pintype "bidirectional"))
    )
    (net (code "16") (name "INT_RTC") (class "Default")
      (node (ref "R1_PINH1") (pin "1") (pinfunction "1_1") (pintype "passive"))
      (node (ref "TP15") (pin "TP") (pinfunction "TP_TP") (pintype "input"))
      (node (ref "U11") (pin "3") (pinfunction "SQW/~{INT}_3") (pintype "output"))
      (node (ref "U21") (pin "8") (pinfunction "IO0_8") (pintype "bidirectional"))
    )
    (net (code "17") (name "IO{slash}BOOT") (class "Default")
      (node (ref "BOOT_BUTTON") (pin "3") (pinfunction "3_3") (pintype "passive"))
      (node (ref "BOOT_BUTTON") (pin "4") (pinfunction "4_4") (pintype "passive"))
      (node (ref "C6") (pin "1") (pinfunction "1_1") (pintype "passive"))
      (node (ref "R_BOOT") (pin "1") (pinfunction "1_1") (pintype "passive"))
      (node (ref "U21") (pin "15") (pinfunction "IO9_15") (pintype "bidirectional"))
    )
    (net (code "18") (name "IO{slash}CHANGE") (class "Default")
      (node (ref "C10") (pin "1") (pinfunction "1_1") (pintype "passive"))
      (node (ref "CHANGE_BUTTON") (pin "3") (pinfunction "3_3") (pintype "passive"))
      (node (ref "CHANGE_BUTTON") (pin "4") (pinfunction "4_4") (pintype "passive"))
      (node (ref "R_CHANGE") (pin "1") (pinfunction "1_1") (pintype "passive"))
      (node (ref "U21") (pin "23") (pinfunction "IO15_23") (pintype "bidirectional"))
    )
    (net (code "19") (name "MISO") (class "Default")
      (node (ref "D12") (pin "2") (pinfunction "2_2") (pintype "passive"))
      (node (ref "J4") (pin "P7") (pinfunction "DAT0_P7") (pintype "bidirectional"))
      (node (ref "R8") (pin "1") (pinfunction "1_1") (pintype "passive"))
      (node (ref "TP6") (pin "TP") (pinfunction "TP_TP") (pintype "input"))
      (node (ref "U1") (pin "2") (pinfunction "DO(IO1)_2") (pintype "bidirectional"))
      (node (ref "U21") (pin "27") (pinfunction "IO2_27") (pintype "bidirectional"))
    )
    (net (code "20") (name "MOSI") (class "Default")
      (node (ref "D13") (pin "2") (pinfunction "2_2") (pintype "passive"))
      (node (ref "J1") (pin "14") (pinfunction "14_14") (pintype "bidirectional"))
      (node (ref "J4") (pin "P3") (pinfunction "CMD_P3") (pintype "bidirectional"))
      (node (ref "R7") (pin "1") (pinfunction "1_1") (pintype "passive"))
      (node (ref "TP7") (pin "TP") (pinfunction "TP_TP") (pintype "input"))
      (node (ref "U1") (pin "5") (pinfunction "DI(IO0)_5") (pintype "bidirectional"))
      (node (ref "U21") (pin "7") (pinfunction "IO7_7") (pintype "bidirectional"))
    )
    (net (code "21") (name "Net-(CHG_LED-PadC)") (class "Default")
      (node (ref "CHG_LED") (pin "C") (pinfunction "C_C") (pintype "passive"))
      (node (ref "R1_BAT") (pin "1") (pinfunction "1_1") (pintype "passive"))
    )
    (net (code "22") (name "Net-(D2-CATHODE)") (class "Default")
      (node (ref "C1_BAT1") (pin "1") (pinfunction "1_1") (pintype "passive"))
      (node (ref "D2") (pin "1") (pinfunction "CATHODE_1") (pintype "bidirectional"))
      (node (ref "IC4") (pin "1") (pinfunction "VIN_1") (pintype "bidirectional"))
      (node (ref "IC4") (pin "3") (pinfunction "CE_3") (pintype "bidirectional"))
      (node (ref "Q1") (pin "2") (pinfunction "S_2") (pintype "bidirectional"))
    )
    (net (code "23") (name "Net-(D3-A)") (class "Default")
      (node (ref "C4") (pin "1") (pinfunction "1_1") (pintype "passive"))
      (node (ref "D3") (pin "2") (pinfunction "A_2") (pintype "bidirectional"))
      (node (ref "D4") (pin "1") (pinfunction "K_1") (pintype "bidirectional"))
    )
    (net (code "24") (name "Net-(D7-CATHODE)") (class "Default")
      (node (ref "D7") (pin "1") (pinfunction "CATHODE_1") (pintype "bidirectional"))
      (node (ref "R_CAPACITOR") (pin "1") (pinfunction "1_1") (pintype "passive"))
    )
    (net (code "25") (name "Net-(EPD_C1-Pad2)") (class "Default")
      (node (ref "EPD_C1") (pin "2") (pinfunction "2_2") (pintype "passive"))
      (node (ref "J1") (pin "4") (pinfunction "4_4") (pintype "bidirectional"))
    )
    (net (code "26") (name "Net-(EPD_C2-Pad2)") (class "Default")
      (node (ref "EPD_C2") (pin "2") (pinfunction "2_2") (pintype "passive"))
      (node (ref "J1") (pin "5") (pinfunction "5_5") (pintype "bidirectional"))
    )
    (net (code "27") (name "Net-(EPD_C6-Pad2)") (class "Default")
      (node (ref "EPD_C6") (pin "2") (pinfunction "2_2") (pintype "passive"))
      (node (ref "J1") (pin "18") (pinfunction "18_18") (pintype "bidirectional"))
    )
    (net (code "28") (name "Net-(EPD_C7-Pad2)") (class "Default")
      (node (ref "EPD_C7") (pin "2") (pinfunction "2_2") (pintype "passive"))
      (node (ref "J1") (pin "19") (pinfunction "19_19") (pintype "bidirectional"))
    )
    (net (code "29") (name "Net-(EPD_C8-Pad2)") (class "Default")
      (node (ref "EPD_C8") (pin "2") (pinfunction "2_2") (pintype "passive"))
      (node (ref "J1") (pin "20") (pinfunction "20_20") (pintype "bidirectional"))
    )
    (net (code "30") (name "Net-(EPD_C10-Pad2)") (class "Default")
      (node (ref "EPD_C10") (pin "2") (pinfunction "2_2") (pintype "passive"))
      (node (ref "J1") (pin "22") (pinfunction "22_22") (pintype "bidirectional"))
    )
    (net (code "31") (name "Net-(EPD_C12-Pad2)") (class "Default")
      (node (ref "EPD_C12") (pin "2") (pinfunction "2_2") (pintype "passive"))
      (node (ref "J1") (pin "24") (pinfunction "24_24") (pintype "bidirectional"))
    )
    (net (code "32") (name "Net-(IC11-CT)") (class "Default")
      (node (ref "C_DELAY") (pin "1") (pinfunction "1_1") (pintype "passive"))
      (node (ref "IC11") (pin "5") (pinfunction "CT_5") (pintype "bidirectional"))
    )
    (net (code "33") (name "Net-(J2-PadA5)") (class "Default")
      (node (ref "J2") (pin "A5") (pinfunction "A5_A5") (pintype "bidirectional"))
      (node (ref "R2-USB1") (pin "2") (pinfunction "2_2") (pintype "passive"))
    )
    (net (code "34") (name "Net-(J2-PadB5)") (class "Default")
      (node (ref "J2") (pin "B5") (pinfunction "B5_B5") (pintype "bidirectional"))
      (node (ref "R2-USB2") (pin "1") (pinfunction "1_1") (pintype "passive"))
    )
    (net (code "35") (name "Net-(J2-PadB12)") (class "Default")
      (node (ref "J2") (pin "B12") (pinfunction "B12_B12") (pintype "bidirectional"))
      (node (ref "J2") (pin "MP1") (pinfunction "MP1_MP1") (pintype "bidirectional"))
      (node (ref "J2") (pin "MP2") (pinfunction "MP2_MP2") (pintype "bidirectional"))
      (node (ref "J2") (pin "MP3") (pinfunction "MP3_MP3") (pintype "bidirectional"))
      (node (ref "J2") (pin "MP4") (pinfunction "MP4_MP4") (pintype "bidirectional"))
    )
    (net (code "36") (name "Net-(MCP73831-PROG)") (class "Default")
      (node (ref "MCP73831") (pin "5") (pinfunction "PROG_5") (pintype "input"))
      (node (ref "R2_BAT") (pin "2") (pinfunction "2_2") (pintype "passive"))
    )
    (net (code "37") (name "Net-(MCP73831-STAT)") (class "Default")
      (node (ref "MCP73831") (pin "1") (pinfunction "STAT_1") (pintype "output"))
      (node (ref "R1_BAT") (pin "2") (pinfunction "2_2") (pintype "passive"))
    )
    (net (code "38") (name "PREVGH") (class "Default")
      (node (ref "D5") (pin "1") (pinfunction "K_1") (pintype "bidirectional"))
      (node (ref "EPD_C9") (pin "2") (pinfunction "2_2") (pintype "passive"))
      (node (ref "J1") (pin "21") (pinfunction "21_21") (pintype "bidirectional"))
    )
    (net (code "39") (name "PREVGL") (class "Default")
      (node (ref "D4") (pin "2") (pinfunction "A_2") (pintype "bidirectional"))
      (node (ref "EPD_C11") (pin "2") (pinfunction "2_2") (pintype "passive"))
      (node (ref "J1") (pin "23") (pinfunction "23_23") (pintype "bidirectional"))
    )
    (net (code "40") (name "RESE") (class "Default")
      (node (ref "J1") (pin "3") (pinfunction "3_3") (pintype "bidirectional"))
      (node (ref "Q3") (pin "2") (pinfunction "S_2") (pintype "bidirectional"))
      (node (ref "R3") (pin "2") (pinfunction "2_2") (pintype "passive"))
    )
    (net (code "41") (name "RESE'") (class "Default")
      (node (ref "R2") (pin "2") (pinfunction "2_2") (pintype "passive"))
      (node (ref "R3") (pin "1") (pinfunction "1_1") (pintype "passive"))
      (node (ref "SJ1") (pin "2") (pinfunction "2_2") (pintype "passive"))
    )
    (net (code "42") (name "RESET") (class "Default")
      (node (ref "C5") (pin "1") (pinfunction "1_1") (pintype "passive"))
      (node (ref "IC11") (pin "1") (pinfunction "VOUT_1") (pintype "bidirectional"))
      (node (ref "RESET_BUTTON") (pin "3") (pinfunction "3_3") (pintype "passive"))
      (node (ref "RESET_BUTTON") (pin "4") (pinfunction "4_4") (pintype "passive"))
      (node (ref "R_RESET") (pin "1") (pinfunction "1_1") (pintype "passive"))
      (node (ref "U21") (pin "3") (pinfunction "EN_3") (pintype "input"))
    )
    (net (code "43") (name "RTC_RST") (class "Default")
      (node (ref "U11") (pin "4") (pinfunction "~{RST}_4") (pintype "input"))
      (node (ref "U21") (pin "16") (pinfunction "IO18_16") (pintype "bidirectional"))
    )
    (net (code "44") (name "RX") (class "Default")
      (node (ref "TP2") (pin "TP") (pinfunction "TP_TP") (pintype "input"))
      (node (ref "U21") (pin "24") (pinfunction "RXD0/GPIO17_24") (pintype "bidirectional"))
    )
    (net (code "45") (name "SCK") (class "Default")
      (node (ref "D10") (pin "2") (pinfunction "2_2") (pintype "passive"))
      (node (ref "J1") (pin "13") (pinfunction "13_13") (pintype "bidirectional"))
      (node (ref "J4") (pin "P2") (pinfunction "CD/DAT3_P2") (pintype "bidirectional"))
      (node (ref "J4") (pin "P5") (pinfunction "CLK_P5") (pintype "bidirectional"))
      (node (ref "R6") (pin "1") (pinfunction "1_1") (pintype "passive"))
      (node (ref "TP8") (pin "TP") (pinfunction "TP_TP") (pintype "input"))
      (node (ref "U1") (pin "6") (pinfunction "CLK_6") (pintype "input"))
      (node (ref "U21") (pin "6") (pinfunction "IO6_6") (pintype "bidirectional"))
    )
    (net (code "46") (name "SCL") (class "Default")
      (node (ref "J3") (pin "4") (pinfunction "4_4") (pintype "passive"))
      (node (ref "R2_PINH") (pin "1") (pinfunction "1_1") (pintype "passive"))
      (node (ref "SENSOR2") (pin "4") (pinfunction "SCK_4") (pintype "input"))
      (node (ref "U11") (pin "16") (pinfunction "SCL_16") (pintype "input"))
      (node (ref "U21") (pin "20") (pinfunction "IO22_20") (pintype "bidirectional"))
      (node (ref "U4") (pin "7") (pinfunction "SCL_7") (pintype "input"))
    )
    (net (code "47") (name "SDA") (class "Default")
      (node (ref "J3") (pin "3") (pinfunction "3_3") (pintype "passive"))
      (node (ref "R1_PINH") (pin "1") (pinfunction "1_1") (pintype "passive"))
      (node (ref "SENSOR2") (pin "3") (pinfunction "SDI_3") (pintype "bidirectional"))
      (node (ref "U11") (pin "15") (pinfunction "SDA_15") (pintype "bidirectional"))
      (node (ref "U21") (pin "19") (pinfunction "IO21_19") (pintype "bidirectional"))
      (node (ref "U4") (pin "8") (pinfunction "SDA_8") (pintype "bidirectional"))
    )
    (net (code "48") (name "SRC") (class "Default")
      (node (ref "C4") (pin "2") (pinfunction "2_2") (pintype "passive"))
      (node (ref "D5") (pin "2") (pinfunction "A_2") (pintype "bidirectional"))
      (node (ref "L1") (pin "1") (pinfunction "1_1") (pintype "passive"))
      (node (ref "Q3") (pin "3") (pinfunction "D_3") (pintype "bidirectional"))
    )
    (net (code "49") (name "SS_SD") (class "Default")
      (node (ref "D8") (pin "2") (pinfunction "2_2") (pintype "passive"))
      (node (ref "R10") (pin "1") (pinfunction "1_1") (pintype "passive"))
      (node (ref "U21") (pin "4") (pinfunction "IO4_4") (pintype "bidirectional"))
    )
    (net (code "50") (name "TX") (class "Default")
      (node (ref "TP1") (pin "TP") (pinfunction "TP_TP") (pintype "input"))
      (node (ref "U21") (pin "25") (pinfunction "TXD0/GPIO16_25") (pintype "bidirectional"))
    )
    (net (code "51") (name "USB_D+") (class "Default")
      (node (ref "D1") (pin "4") (pinfunction "I/O2_2_4") (pintype "bidirectional"))
      (node (ref "U21") (pin "14") (pinfunction "IO13_14") (pintype "bidirectional"))
    )
    (net (code "52") (name "USB_D-") (class "Default")
      (node (ref "D1") (pin "6") (pinfunction "I/O1_2_6") (pintype "bidirectional"))
      (node (ref "U21") (pin "13") (pinfunction "IO12_13") (pintype "bidirectional"))
    )
    (net (code "53") (name "VBAT") (class "Default")
      (node (ref "C2_BAT") (pin "1") (pinfunction "1_1") (pintype "passive"))
      (node (ref "MCP73831") (pin "3") (pinfunction "VBAT_3") (pintype "power_in"))
      (node (ref "Q1") (pin "3") (pinfunction "D_3") (pintype "bidirectional"))
      (node (ref "TP3") (pin "TP") (pinfunction "TP_TP") (pintype "input"))
      (node (ref "U4") (pin "2") (pinfunction "CELL_2") (pintype "power_in"))
      (node (ref "U4") (pin "3") (pinfunction "VDD_3") (pintype "power_in"))
    )
    (net (code "54") (name "VBUS") (class "Default")
      (node (ref "C1_BAT") (pin "1") (pinfunction "1_1") (pintype "passive"))
      (node (ref "C4_USB") (pin "1") (pinfunction "1_1") (pintype "passive"))
      (node (ref "C5_USB") (pin "1") (pinfunction "1_1") (pintype "passive"))
      (node (ref "CHG_LED") (pin "A") (pinfunction "A_A") (pintype "passive"))
      (node (ref "D1") (pin "2") (pinfunction "GND_2") (pintype "bidirectional"))
      (node (ref "D2") (pin "2") (pinfunction "ANODE_2") (pintype "bidirectional"))
      (node (ref "MCP73831") (pin "4") (pinfunction "VIN_4") (pintype "power_in"))
      (node (ref "PFMF.050.1") (pin "2") (pinfunction "2_2") (pintype "passive"))
      (node (ref "Q1") (pin "1") (pinfunction "G_1") (pintype "bidirectional"))
      (node (ref "R1-PWRUSB") (pin "2") (pinfunction "2_2") (pintype "passive"))
      (node (ref "TP14") (pin "TP") (pinfunction "TP_TP") (pintype "input"))
    )
    (net (code "55") (name "VRTC") (class "Default")
      (node (ref "C10_SUPERCAP") (pin "2") (pinfunction "2_2") (pintype "passive"))
      (node (ref "C8") (pin "1") (pinfunction "1_1") (pintype "passive"))
      (node (ref "R_CAPACITOR") (pin "2") (pinfunction "2_2") (pintype "passive"))
      (node (ref "U11") (pin "14") (pinfunction "VBAT_14") (pintype "power_in"))
    )
    (net (code "56") (name "VUSB") (class "Default")
      (node (ref "J2") (pin "A4") (pinfunction "A4_A4") (pintype "bidirectional"))
      (node (ref "J2") (pin "A9") (pinfunction "A9_A9") (pintype "bidirectional"))
      (node (ref "J2") (pin "B4") (pinfunction "B4_B4") (pintype "bidirectional"))
      (node (ref "J2") (pin "B9") (pinfunction "B9_B9") (pintype "bidirectional"))
      (node (ref "PFMF.050.1") (pin "1") (pinfunction "1_1") (pintype "passive"))
    )
    (net (code "57") (name "unconnected-(IC4-NC-Pad4)") (class "Default")
      (node (ref "IC4") (pin "4") (pinfunction "NC_4") (pintype "no_connect"))
    )
    (net (code "58") (name "unconnected-(IC11-NC-Pad4)") (class "Default")
      (node (ref "IC11") (pin "4") (pinfunction "NC_4") (pintype "no_connect"))
    )
    (net (code "59") (name "unconnected-(J1-Pad1)") (class "Default")
      (node (ref "J1") (pin "1") (pinfunction "1_1") (pintype "bidirectional"))
    )
    (net (code "60") (name "unconnected-(J1-Pad6)") (class "Default")
      (node (ref "J1") (pin "6") (pinfunction "6_6") (pintype "bidirectional"))
    )
    (net (code "61") (name "unconnected-(J1-Pad7)") (class "Default")
      (node (ref "J1") (pin "7") (pinfunction "7_7") (pintype "bidirectional"))
    )
    (net (code "62") (name "unconnected-(J2-PadA8)") (class "Default")
      (node (ref "J2") (pin "A8") (pinfunction "A8_A8") (pintype "bidirectional"))
    )
    (net (code "63") (name "unconnected-(J2-PadB8)") (class "Default")
      (node (ref "J2") (pin "B8") (pinfunction "B8_B8") (pintype "bidirectional"))
    )
    (net (code "64") (name "unconnected-(J4-DAT1-PadP8)") (class "Default")
      (node (ref "J4") (pin "P8") (pinfunction "DAT1_P8") (pintype "bidirectional"))
    )
    (net (code "65") (name "unconnected-(J4-DAT2-PadP1)") (class "Default")
      (node (ref "J4") (pin "P1") (pinfunction "DAT2_P1") (pintype "bidirectional"))
    )
    (net (code "66") (name "unconnected-(J4-DETECTION_1-PadS1)") (class "Default")
      (node (ref "J4") (pin "S1") (pinfunction "DETECTION_1_S1") (pintype "bidirectional"))
    )
    (net (code "67") (name "unconnected-(J4-DETECTION_2-PadS2)") (class "Default")
      (node (ref "J4") (pin "S2") (pinfunction "DETECTION_2_S2") (pintype "bidirectional"))
    )
    (net (code "68") (name "unconnected-(U4-~{ALERT}-Pad5)") (class "Default")
      (node (ref "U4") (pin "5") (pinfunction "~{ALERT}_5") (pintype "output"))
    )
    (net (code "69") (name "unconnected-(U21-NC-Pad22)") (class "Default")
      (node (ref "U21") (pin "22") (pinfunction "NC_22") (pintype "no_connect"))
    )
  )
)
